# spdif2analog.net
KiCad netlist of a schematic drawn in EAGLE
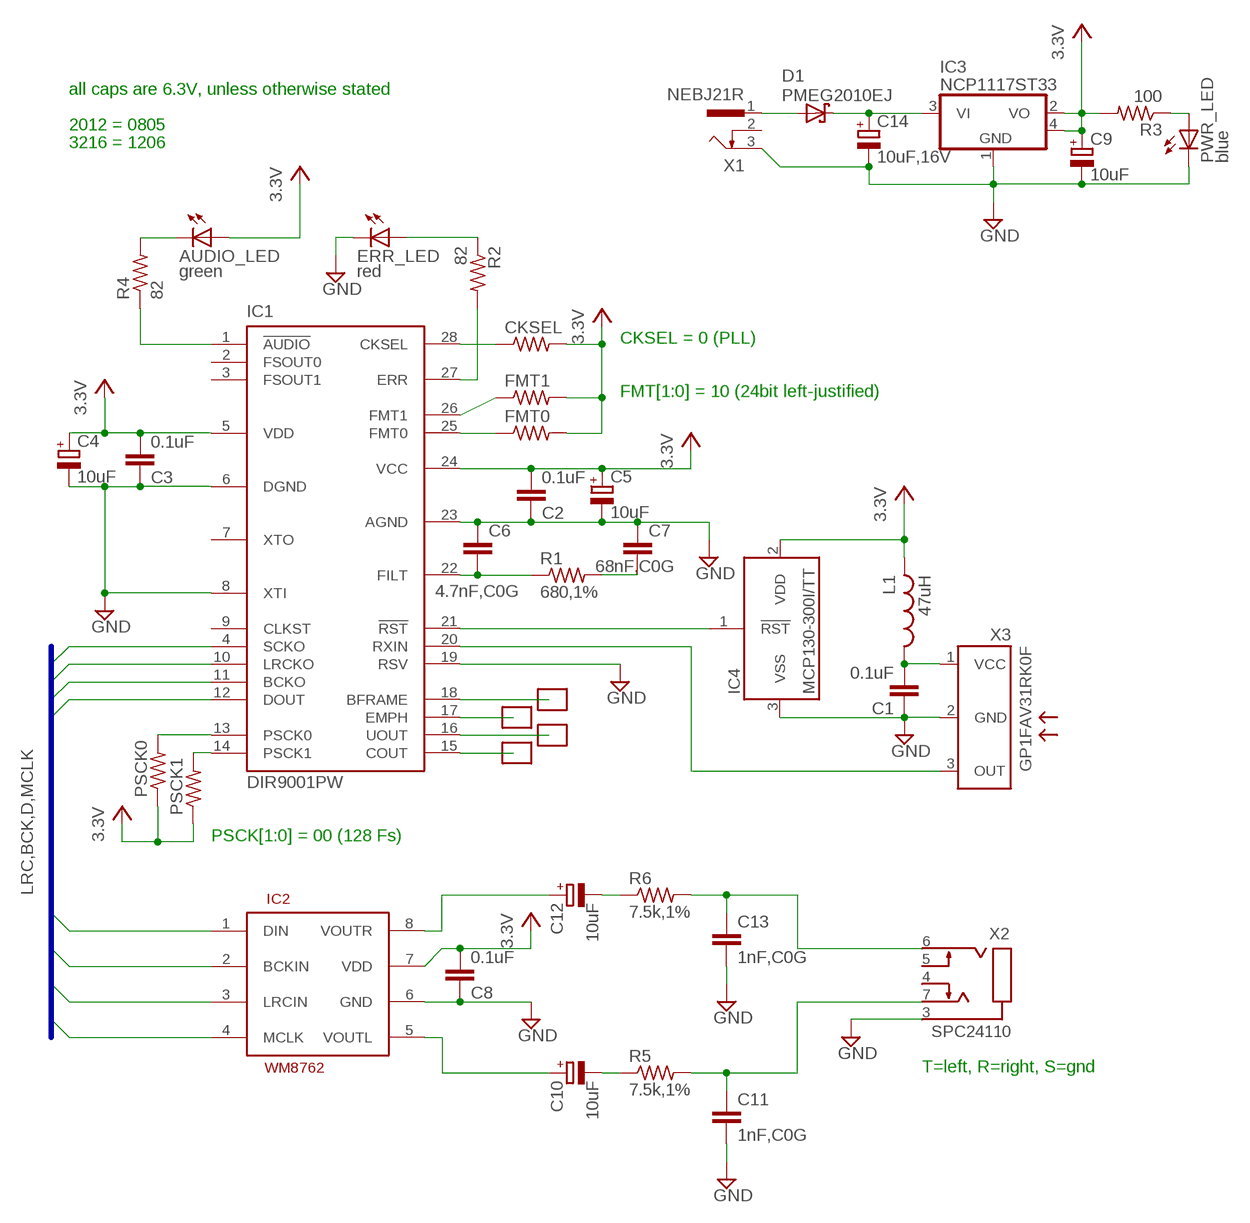
[diagram p0: schematic, sheet 1]

(export (version "E")
  (design (tool "Eeschema 10.0.6"))
  (components
    (comp (ref "AUDIO_LED")
      (value "green")
      (footprint "eagle-import:CHIPLED_0805")
      (libsource (lib "eagle-import") (part "LEDCHIPLED_0805"))
    )
    (comp (ref "C1")
      (value "0.1uF")
      (footprint "eagle-import:C0805")
      (libsource (lib "eagle-import") (part "C-EUC0805"))
    )
    (comp (ref "C2")
      (value "0.1uF")
      (footprint "eagle-import:C0805")
      (libsource (lib "eagle-import") (part "C-EUC0805"))
    )
    (comp (ref "C3")
      (value "0.1uF")
      (footprint "eagle-import:C0805")
      (libsource (lib "eagle-import") (part "C-EUC0805"))
    )
    (comp (ref "C4")
      (value "10uF")
      (footprint "eagle-import:A_3216-18R")
      (libsource (lib "eagle-import") (part "CPOL-EUA/3216-18R"))
    )
    (comp (ref "C5")
      (value "10uF")
      (footprint "eagle-import:A_3216-18R")
      (libsource (lib "eagle-import") (part "CPOL-EUA/3216-18R"))
    )
    (comp (ref "C6")
      (value "4.7nF,C0G")
      (footprint "eagle-import:C0805")
      (libsource (lib "eagle-import") (part "C-EUC0805"))
    )
    (comp (ref "C7")
      (value "68nF,C0G")
      (footprint "eagle-import:C025_050-035X075")
      (libsource (lib "eagle-import") (part "C-EU025_050-035X075"))
    )
    (comp (ref "C8")
      (value "0.1uF")
      (footprint "eagle-import:C0805")
      (libsource (lib "eagle-import") (part "C-EUC0805"))
    )
    (comp (ref "C9")
      (value "10uF")
      (footprint "eagle-import:A_3216-18R")
      (libsource (lib "eagle-import") (part "CPOL-EUA/3216-18R"))
    )
    (comp (ref "C10")
      (value "10uF")
      (footprint "eagle-import:A_3216-18R")
      (libsource (lib "eagle-import") (part "CPOL-EUA/3216-18R"))
    )
    (comp (ref "C11")
      (value "1nF,C0G")
      (footprint "eagle-import:C0805")
      (libsource (lib "eagle-import") (part "C-EUC0805"))
    )
    (comp (ref "C12")
      (value "10uF")
      (footprint "eagle-import:A_3216-18R")
      (libsource (lib "eagle-import") (part "CPOL-EUA/3216-18R"))
    )
    (comp (ref "C13")
      (value "1nF,C0G")
      (footprint "eagle-import:C0805")
      (libsource (lib "eagle-import") (part "C-EUC0805"))
    )
    (comp (ref "C14")
      (value "10uF,16V")
      (footprint "eagle-import:A_3216-18R")
      (libsource (lib "eagle-import") (part "CPOL-EUA/3216-18R"))
    )
    (comp (ref "CKSEL")
      (value "5.1k")
      (footprint "eagle-import:R0805")
      (libsource (lib "eagle-import") (part "R-US_R0805"))
    )
    (comp (ref "D1")
      (value "PMEG2010EJ")
      (footprint "eagle-import:SOD-323")
      (libsource (lib "eagle-import") (part "PMEG2010EJ"))
    )
    (comp (ref "ERR_LED")
      (value "red")
      (footprint "eagle-import:CHIPLED_0805")
      (libsource (lib "eagle-import") (part "LEDCHIPLED_0805"))
    )
    (comp (ref "FMT0")
      (value "5.1k")
      (footprint "eagle-import:R0805")
      (libsource (lib "eagle-import") (part "R-US_R0805"))
    )
    (comp (ref "FMT1")
      (value "5.1k")
      (footprint "eagle-import:R0805")
      (libsource (lib "eagle-import") (part "R-US_R0805"))
    )
    (comp (ref "IC1")
      (value "DIR9001PW")
      (footprint "eagle-import:PW_R-PDSO-G28")
      (libsource (lib "eagle-import") (part "DIR9001PW"))
    )
    (comp (ref "IC2")
      (value "WM8762")
      (footprint "eagle-import:SOIC8")
      (libsource (lib "eagle-import") (part "WM8762"))
    )
    (comp (ref "IC3")
      (value "NCP1117ST33")
      (footprint "eagle-import:SOT-223")
      (libsource (lib "eagle-import") (part "NCP1117ST33"))
    )
    (comp (ref "IC4")
      (value "MCP130-300I/TT")
      (footprint "eagle-import:SOT-23-3")
      (libsource (lib "eagle-import") (part "MCP130-I/TT300"))
    )
    (comp (ref "L1")
      (value "47uH")
      (footprint "eagle-import:L2012C")
      (libsource (lib "eagle-import") (part "L-USL2012C"))
    )
    (comp (ref "PSCK0")
      (value "5.1k")
      (footprint "eagle-import:R0805")
      (libsource (lib "eagle-import") (part "R-US_R0805"))
    )
    (comp (ref "PSCK1")
      (value "5.1k")
      (footprint "eagle-import:R0805")
      (libsource (lib "eagle-import") (part "R-US_R0805"))
    )
    (comp (ref "PWR_LED")
      (value "blue")
      (footprint "eagle-import:CHIPLED_0805")
      (libsource (lib "eagle-import") (part "LEDCHIPLED_0805"))
    )
    (comp (ref "R1")
      (value "680,1%")
      (footprint "eagle-import:R0805")
      (libsource (lib "eagle-import") (part "R-US_R0805"))
    )
    (comp (ref "R2")
      (value "82")
      (footprint "eagle-import:R0805")
      (libsource (lib "eagle-import") (part "R-US_R0805"))
    )
    (comp (ref "R3")
      (value "100")
      (footprint "eagle-import:R0805")
      (libsource (lib "eagle-import") (part "R-US_R0805"))
    )
    (comp (ref "R4")
      (value "82")
      (footprint "eagle-import:R0805")
      (libsource (lib "eagle-import") (part "R-US_R0805"))
    )
    (comp (ref "R5")
      (value "7.5k,1%")
      (footprint "eagle-import:R0805")
      (libsource (lib "eagle-import") (part "R-US_R0805"))
    )
    (comp (ref "R6")
      (value "7.5k,1%")
      (footprint "eagle-import:R0805")
      (libsource (lib "eagle-import") (part "R-US_R0805"))
    )
    (comp (ref "U$1")
      (value "PAD.015")
      (footprint "eagle-import:PAD.015")
      (libsource (lib "eagle-import") (part "PAD.015"))
    )
    (comp (ref "U$2")
      (value "PAD.015")
      (footprint "eagle-import:PAD.015")
      (libsource (lib "eagle-import") (part "PAD.015"))
    )
    (comp (ref "U$3")
      (value "PAD.015")
      (footprint "eagle-import:PAD.015")
      (libsource (lib "eagle-import") (part "PAD.015"))
    )
    (comp (ref "U$4")
      (value "PAD.015")
      (footprint "eagle-import:PAD.015")
      (libsource (lib "eagle-import") (part "PAD.015"))
    )
    (comp (ref "X1")
      (value "NEBJ21R")
      (footprint "eagle-import:NEBJ21R")
      (fields (field (name "MPN") "NEB/J 21 R"))
      (libsource (lib "eagle-import") (part "NEBJ21R"))
    )
    (comp (ref "X2")
      (value "SPC24110")
      (footprint "eagle-import:SPC24110")
      (libsource (lib "eagle-import") (part "SPC24110"))
    )
    (comp (ref "X3")
      (value "GP1FAV31RK0F")
      (footprint "eagle-import:GP1FAV31RK0F")
      (libsource (lib "eagle-import") (part "GP1FAV1RK0F3"))
    )
  )
  (nets
    (net (code "1") (name "/BCK") (class "Default")
      (node (ref "IC1") (pin "11") (pinfunction "BCKO_11") (pintype "output"))
      (node (ref "IC2") (pin "2") (pinfunction "BCKIN_2") (pintype "input"))
    )
    (net (code "2") (name "/D") (class "Default")
      (node (ref "IC1") (pin "12") (pinfunction "DOUT_12") (pintype "output"))
      (node (ref "IC2") (pin "1") (pinfunction "DIN_1") (pintype "input"))
    )
    (net (code "3") (name "/LRC") (class "Default")
      (node (ref "IC1") (pin "10") (pinfunction "LRCKO_10") (pintype "output"))
      (node (ref "IC2") (pin "3") (pinfunction "LRCIN_3") (pintype "input"))
    )
    (net (code "4") (name "/MCLK") (class "Default")
      (node (ref "IC1") (pin "4") (pinfunction "SCKO_4") (pintype "output"))
      (node (ref "IC2") (pin "4") (pinfunction "MCLK_4") (pintype "input"))
    )
    (net (code "6") (name "3.3V") (class "Default")
      (node (ref "AUDIO_LED") (pin "A") (pinfunction "A_A") (pintype "passive"))
      (node (ref "C2") (pin "2") (pinfunction "2_2") (pintype "passive"))
      (node (ref "C3") (pin "2") (pinfunction "2_2") (pintype "passive"))
      (node (ref "C4") (pin "+") (pinfunction "+_+") (pintype "passive"))
      (node (ref "C5") (pin "+") (pinfunction "+_+") (pintype "passive"))
      (node (ref "C8") (pin "2") (pinfunction "2_2") (pintype "passive"))
      (node (ref "C9") (pin "+") (pinfunction "+_+") (pintype "passive"))
      (node (ref "CKSEL") (pin "2") (pinfunction "2_2") (pintype "passive"))
      (node (ref "FMT0") (pin "2") (pinfunction "2_2") (pintype "passive"))
      (node (ref "FMT1") (pin "2") (pinfunction "2_2") (pintype "passive"))
      (node (ref "IC1") (pin "24") (pinfunction "VCC_24") (pintype "power_in"))
      (node (ref "IC1") (pin "5") (pinfunction "VDD_5") (pintype "power_in"))
      (node (ref "IC2") (pin "7") (pinfunction "VDD_7") (pintype "power_in"))
      (node (ref "IC3") (pin "2") (pinfunction "VO_2") (pintype "passive"))
      (node (ref "IC3") (pin "4") (pinfunction "TAB_4") (pintype "passive"))
      (node (ref "IC4") (pin "2") (pinfunction "VDD_2") (pintype "power_in"))
      (node (ref "L1") (pin "2") (pinfunction "2_2") (pintype "passive"))
      (node (ref "PSCK0") (pin "1") (pinfunction "1_1") (pintype "passive"))
      (node (ref "PSCK1") (pin "1") (pinfunction "1_1") (pintype "passive"))
      (node (ref "R3") (pin "2") (pinfunction "2_2") (pintype "passive"))
    )
    (net (code "7") (name "GND") (class "Default")
      (node (ref "C1") (pin "1") (pinfunction "1_1") (pintype "passive"))
      (node (ref "C11") (pin "2") (pinfunction "2_2") (pintype "passive"))
      (node (ref "C13") (pin "2") (pinfunction "2_2") (pintype "passive"))
      (node (ref "C14") (pin "-") (pinfunction "-_-") (pintype "passive"))
      (node (ref "C2") (pin "1") (pinfunction "1_1") (pintype "passive"))
      (node (ref "C3") (pin "1") (pinfunction "1_1") (pintype "passive"))
      (node (ref "C4") (pin "-") (pinfunction "-_-") (pintype "passive"))
      (node (ref "C5") (pin "-") (pinfunction "-_-") (pintype "passive"))
      (node (ref "C6") (pin "1") (pinfunction "1_1") (pintype "passive"))
      (node (ref "C7") (pin "1") (pinfunction "1_1") (pintype "passive"))
      (node (ref "C8") (pin "1") (pinfunction "1_1") (pintype "passive"))
      (node (ref "C9") (pin "-") (pinfunction "-_-") (pintype "passive"))
      (node (ref "ERR_LED") (pin "C") (pinfunction "C_C") (pintype "passive"))
      (node (ref "IC1") (pin "19") (pinfunction "RSV_19") (pintype "power_in"))
      (node (ref "IC1") (pin "23") (pinfunction "AGND_23") (pintype "power_in"))
      (node (ref "IC1") (pin "6") (pinfunction "DGND_6") (pintype "power_in"))
      (node (ref "IC1") (pin "8") (pinfunction "XTI_8") (pintype "bidirectional"))
      (node (ref "IC2") (pin "6") (pinfunction "GND_6") (pintype "power_in"))
      (node (ref "IC3") (pin "1") (pinfunction "GND_1") (pintype "passive"))
      (node (ref "IC4") (pin "3") (pinfunction "VSS_3") (pintype "power_in"))
      (node (ref "PWR_LED") (pin "C") (pinfunction "C_C") (pintype "passive"))
      (node (ref "X1") (pin "3") (pinfunction "3_3") (pintype "passive"))
      (node (ref "X2") (pin "3") (pinfunction "SLEEVE_3") (pintype "passive"))
      (node (ref "X3") (pin "2") (pinfunction "GND_2") (pintype "power_in"))
    )
    (net (code "8") (name "Net-(AUDIO_LED-PadC)") (class "Default")
      (node (ref "AUDIO_LED") (pin "C") (pinfunction "C_C") (pintype "passive"))
      (node (ref "R4") (pin "2") (pinfunction "2_2") (pintype "passive"))
    )
    (net (code "9") (name "Net-(C7-Pad2)") (class "Default")
      (node (ref "C7") (pin "2") (pinfunction "2_2") (pintype "passive"))
      (node (ref "R1") (pin "2") (pinfunction "2_2") (pintype "passive"))
    )
    (net (code "10") (name "Net-(C10-Pad-)") (class "Default")
      (node (ref "C10") (pin "-") (pinfunction "-_-") (pintype "passive"))
      (node (ref "R5") (pin "1") (pinfunction "1_1") (pintype "passive"))
    )
    (net (code "11") (name "Net-(C12-Pad-)") (class "Default")
      (node (ref "C12") (pin "-") (pinfunction "-_-") (pintype "passive"))
      (node (ref "R6") (pin "1") (pinfunction "1_1") (pintype "passive"))
    )
    (net (code "12") (name "Net-(D1-A)") (class "Default")
      (node (ref "D1") (pin "2") (pinfunction "A_2") (pintype "passive"))
      (node (ref "X1") (pin "1") (pinfunction "1_1") (pintype "passive"))
    )
    (net (code "13") (name "Net-(D1-C)") (class "Default")
      (node (ref "C14") (pin "+") (pinfunction "+_+") (pintype "passive"))
      (node (ref "D1") (pin "1") (pinfunction "C_1") (pintype "passive"))
      (node (ref "IC3") (pin "3") (pinfunction "VI_3") (pintype "input"))
    )
    (net (code "14") (name "Net-(ERR_LED-PadA)") (class "Default")
      (node (ref "ERR_LED") (pin "A") (pinfunction "A_A") (pintype "passive"))
      (node (ref "R2") (pin "1") (pinfunction "1_1") (pintype "passive"))
    )
    (net (code "15") (name "Net-(IC1-BFRAME)") (class "Default")
      (node (ref "IC1") (pin "18") (pinfunction "BFRAME_18") (pintype "output"))
      (node (ref "U$1") (pin "1") (pinfunction "P_1") (pintype "bidirectional"))
    )
    (net (code "16") (name "Net-(IC1-CKSEL)") (class "Default")
      (node (ref "CKSEL") (pin "1") (pinfunction "1_1") (pintype "passive"))
      (node (ref "IC1") (pin "28") (pinfunction "CKSEL_28") (pintype "tri_state"))
    )
    (net (code "17") (name "Net-(IC1-COUT)") (class "Default")
      (node (ref "IC1") (pin "15") (pinfunction "COUT_15") (pintype "output"))
      (node (ref "U$4") (pin "1") (pinfunction "P_1") (pintype "bidirectional"))
    )
    (net (code "18") (name "Net-(IC1-EMPH)") (class "Default")
      (node (ref "IC1") (pin "17") (pinfunction "EMPH_17") (pintype "output"))
      (node (ref "U$2") (pin "1") (pinfunction "P_1") (pintype "bidirectional"))
    )
    (net (code "19") (name "Net-(IC1-ERR)") (class "Default")
      (node (ref "IC1") (pin "27") (pinfunction "ERR_27") (pintype "output"))
      (node (ref "R2") (pin "2") (pinfunction "2_2") (pintype "passive"))
    )
    (net (code "20") (name "Net-(IC1-FILT)") (class "Default")
      (node (ref "C6") (pin "2") (pinfunction "2_2") (pintype "passive"))
      (node (ref "IC1") (pin "22") (pinfunction "FILT_22") (pintype "bidirectional"))
      (node (ref "R1") (pin "1") (pinfunction "1_1") (pintype "passive"))
    )
    (net (code "21") (name "Net-(IC1-FMT0)") (class "Default")
      (node (ref "FMT0") (pin "1") (pinfunction "1_1") (pintype "passive"))
      (node (ref "IC1") (pin "25") (pinfunction "FMT0_25") (pintype "tri_state"))
    )
    (net (code "22") (name "Net-(IC1-FMT1)") (class "Default")
      (node (ref "FMT1") (pin "1") (pinfunction "1_1") (pintype "passive"))
      (node (ref "IC1") (pin "26") (pinfunction "FMT1_26") (pintype "tri_state"))
    )
    (net (code "23") (name "Net-(IC1-PSCK0)") (class "Default")
      (node (ref "IC1") (pin "13") (pinfunction "PSCK0_13") (pintype "tri_state"))
      (node (ref "PSCK0") (pin "2") (pinfunction "2_2") (pintype "passive"))
    )
    (net (code "24") (name "Net-(IC1-PSCK1)") (class "Default")
      (node (ref "IC1") (pin "14") (pinfunction "PSCK1_14") (pintype "tri_state"))
      (node (ref "PSCK1") (pin "2") (pinfunction "2_2") (pintype "passive"))
    )
    (net (code "25") (name "Net-(IC1-RXIN)") (class "Default")
      (node (ref "IC1") (pin "20") (pinfunction "RXIN_20") (pintype "input"))
      (node (ref "X3") (pin "3") (pinfunction "OUT_3") (pintype "output"))
    )
    (net (code "26") (name "Net-(IC1-UOUT)") (class "Default")
      (node (ref "IC1") (pin "16") (pinfunction "UOUT_16") (pintype "output"))
      (node (ref "U$3") (pin "1") (pinfunction "P_1") (pintype "bidirectional"))
    )
    (net (code "27") (name "Net-(IC1-~{AUDIO})") (class "Default")
      (node (ref "IC1") (pin "1") (pinfunction "~{AUDIO}_1") (pintype "output"))
      (node (ref "R4") (pin "1") (pinfunction "1_1") (pintype "passive"))
    )
    (net (code "28") (name "Net-(IC1-~{RST})") (class "Default")
      (node (ref "IC1") (pin "21") (pinfunction "~{RST}_21") (pintype "input"))
      (node (ref "IC4") (pin "1") (pinfunction "~{RST}_1") (pintype "output"))
    )
    (net (code "29") (name "Net-(IC2-VOUTL)") (class "Default")
      (node (ref "C10") (pin "+") (pinfunction "+_+") (pintype "passive"))
      (node (ref "IC2") (pin "5") (pinfunction "VOUTL_5") (pintype "output"))
    )
    (net (code "30") (name "Net-(IC2-VOUTR)") (class "Default")
      (node (ref "C12") (pin "+") (pinfunction "+_+") (pintype "passive"))
      (node (ref "IC2") (pin "8") (pinfunction "VOUTR_8") (pintype "output"))
    )
    (net (code "31") (name "Net-(PWR_LED-PadA)") (class "Default")
      (node (ref "PWR_LED") (pin "A") (pinfunction "A_A") (pintype "passive"))
      (node (ref "R3") (pin "1") (pinfunction "1_1") (pintype "passive"))
    )
    (net (code "32") (name "Net-(X2-RING)") (class "Default")
      (node (ref "C13") (pin "1") (pinfunction "1_1") (pintype "passive"))
      (node (ref "R6") (pin "2") (pinfunction "2_2") (pintype "passive"))
      (node (ref "X2") (pin "6") (pinfunction "RING_6") (pintype "passive"))
    )
    (net (code "33") (name "Net-(X2-TIP)") (class "Default")
      (node (ref "C11") (pin "1") (pinfunction "1_1") (pintype "passive"))
      (node (ref "R5") (pin "2") (pinfunction "2_2") (pintype "passive"))
      (node (ref "X2") (pin "7") (pinfunction "TIP_7") (pintype "passive"))
    )
    (net (code "34") (name "Net-(X3-VCC)") (class "Default")
      (node (ref "C1") (pin "2") (pinfunction "2_2") (pintype "passive"))
      (node (ref "L1") (pin "1") (pinfunction "1_1") (pintype "passive"))
      (node (ref "X3") (pin "1") (pinfunction "VCC_1") (pintype "power_in"))
    )
    (net (code "35") (name "unconnected-(IC1-CLKST-Pad9)") (class "Default")
      (node (ref "IC1") (pin "9") (pinfunction "CLKST_9") (pintype "output"))
    )
    (net (code "36") (name "unconnected-(IC1-FSOUT0-Pad2)") (class "Default")
      (node (ref "IC1") (pin "2") (pinfunction "FSOUT0_2") (pintype "output"))
    )
    (net (code "37") (name "unconnected-(IC1-FSOUT1-Pad3)") (class "Default")
      (node (ref "IC1") (pin "3") (pinfunction "FSOUT1_3") (pintype "output"))
    )
    (net (code "38") (name "unconnected-(IC1-XTO-Pad7)") (class "Default")
      (node (ref "IC1") (pin "7") (pinfunction "XTO_7") (pintype "bidirectional"))
    )
    (net (code "39") (name "unconnected-(X1-Pad2)") (class "Default")
      (node (ref "X1") (pin "2") (pinfunction "2_2") (pintype "passive"))
    )
    (net (code "40") (name "unconnected-(X2-SHUNT_A-Pad5)") (class "Default")
      (node (ref "X2") (pin "5") (pinfunction "SHUNT_A_5") (pintype "passive"))
    )
    (net (code "41") (name "unconnected-(X2-SHUNT_B-Pad4)") (class "Default")
      (node (ref "X2") (pin "4") (pinfunction "SHUNT_B_4") (pintype "passive"))
    )
  )
)
